# Zio_Qwiic_Air_Pressure_Sensor_BMP280.net
KiCad netlist of a schematic drawn in EAGLE
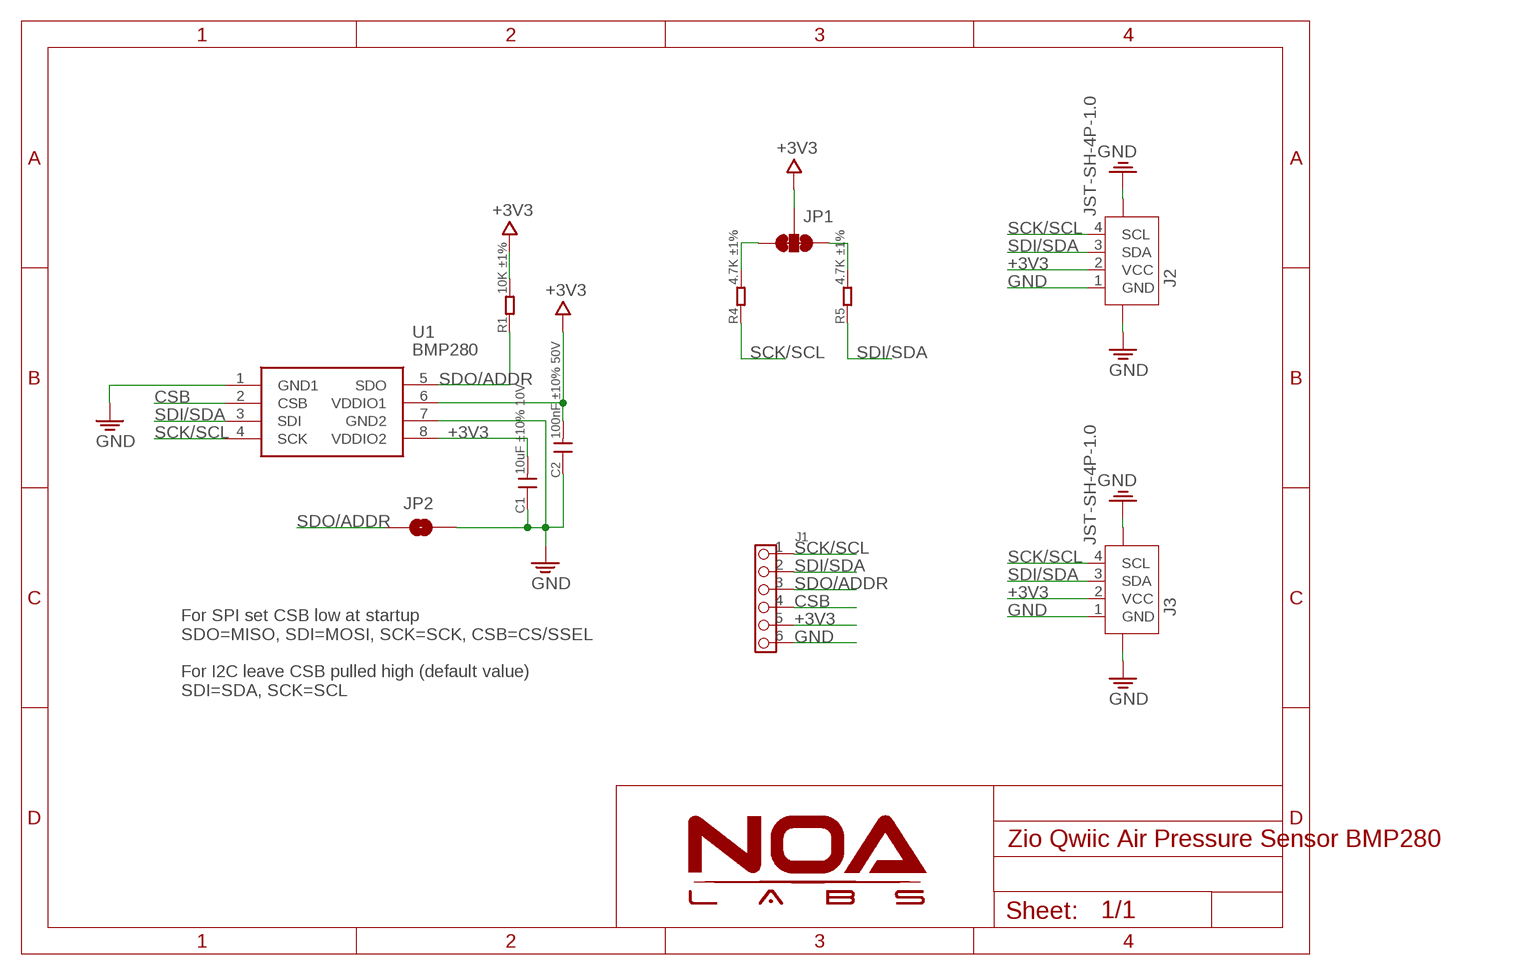
[diagram p0: schematic, sheet 1]

(export (version "E")
  (design (tool "Eeschema 10.0.6"))
  (components
    (comp (ref "C1")
      (value "10uF ±10% 10V")
      (footprint "eagle-import:C0603")
      (libsource (lib "eagle-import") (part "C-0603"))
    )
    (comp (ref "C2")
      (value "100nF ±10% 50V")
      (footprint "eagle-import:C0603")
      (libsource (lib "eagle-import") (part "C-0603"))
    )
    (comp (ref "J1")
      (value "HEADER-6P-60/35MIL")
      (footprint "eagle-import:6P-2.54-60_35MIL")
      (libsource (lib "eagle-import") (part "HEADER-6P-60/35MIL"))
    )
    (comp (ref "J2")
      (value "JST-SH-4P-1.0")
      (footprint "eagle-import:JST-SH-4P")
      (libsource (lib "eagle-import") (part "JST-SH-4P-1.0"))
    )
    (comp (ref "J3")
      (value "JST-SH-4P-1.0")
      (footprint "eagle-import:JST-SH-4P")
      (libsource (lib "eagle-import") (part "JST-SH-4P-1.0"))
    )
    (comp (ref "JP1")
      (value "SMT-JUMPER_3_2-NC_TRACE")
      (footprint "eagle-import:SMT-JUMPER_3_2-NC_TRACE")
      (libsource (lib "eagle-import") (part "SMT-JUMPER_3_2-NC_TRACE"))
    )
    (comp (ref "JP2")
      (value "JUMPER-SMT_2_NC_PASTE_NOCREM")
      (footprint "eagle-import:SMT-JUMPER_2_NC_PASTE_SILK_NOCREM")
      (libsource (lib "eagle-import") (part "JUMPER-SMT_2_NC_PASTE_NOCREM"))
    )
    (comp (ref "R1")
      (value "10K ±1%")
      (footprint "eagle-import:R0603")
      (libsource (lib "eagle-import") (part "R-0603"))
    )
    (comp (ref "R4")
      (value "4.7K ±1%")
      (footprint "eagle-import:R0603")
      (libsource (lib "eagle-import") (part "R-0603"))
    )
    (comp (ref "R5")
      (value "4.7K ±1%")
      (footprint "eagle-import:R0603")
      (libsource (lib "eagle-import") (part "R-0603"))
    )
    (comp (ref "U1")
      (value "BMP280")
      (footprint "eagle-import:8-PIN-METAL-LID-LGA")
      (fields (field (name "ARROW_PART_NUMBER") "bmp280"))
      (libsource (lib "eagle-import") (part "BMP280"))
    )
  )
  (nets
    (net (code "1") (name "+3V3") (class "Default")
      (node (ref "C1") (pin "2") (pinfunction "2_2") (pintype "passive"))
      (node (ref "C2") (pin "2") (pinfunction "2_2") (pintype "passive"))
      (node (ref "J1") (pin "5") (pinfunction "5_5") (pintype "bidirectional"))
      (node (ref "J2") (pin "2") (pinfunction "VCC_2") (pintype "bidirectional"))
      (node (ref "J3") (pin "2") (pinfunction "VCC_2") (pintype "bidirectional"))
      (node (ref "JP1") (pin "2") (pinfunction "2_2") (pintype "passive"))
      (node (ref "R1") (pin "2") (pinfunction "2_2") (pintype "passive"))
      (node (ref "U1") (pin "6") (pinfunction "VDDIO1_6") (pintype "power_in"))
      (node (ref "U1") (pin "8") (pinfunction "VDDIO2_8") (pintype "power_in"))
    )
    (net (code "2") (name "/CSB") (class "Default")
      (node (ref "J1") (pin "4") (pinfunction "4_4") (pintype "bidirectional"))
      (node (ref "U1") (pin "2") (pinfunction "CSB_2") (pintype "input"))
    )
    (net (code "3") (name "/SCK{slash}SCL") (class "Default")
      (node (ref "J1") (pin "1") (pinfunction "1_1") (pintype "bidirectional"))
      (node (ref "J2") (pin "4") (pinfunction "SCL_4") (pintype "bidirectional"))
      (node (ref "J3") (pin "4") (pinfunction "SCL_4") (pintype "bidirectional"))
      (node (ref "R4") (pin "1") (pinfunction "1_1") (pintype "passive"))
      (node (ref "U1") (pin "4") (pinfunction "SCK_4") (pintype "bidirectional"))
    )
    (net (code "4") (name "/SDI{slash}SDA") (class "Default")
      (node (ref "J1") (pin "2") (pinfunction "2_2") (pintype "bidirectional"))
      (node (ref "J2") (pin "3") (pinfunction "SDA_3") (pintype "bidirectional"))
      (node (ref "J3") (pin "3") (pinfunction "SDA_3") (pintype "bidirectional"))
      (node (ref "R5") (pin "1") (pinfunction "1_1") (pintype "passive"))
      (node (ref "U1") (pin "3") (pinfunction "SDI_3") (pintype "bidirectional"))
    )
    (net (code "5") (name "/SDO{slash}ADDR") (class "Default")
      (node (ref "J1") (pin "3") (pinfunction "3_3") (pintype "bidirectional"))
      (node (ref "JP2") (pin "1") (pinfunction "1_1") (pintype "passive"))
      (node (ref "R1") (pin "1") (pinfunction "1_1") (pintype "passive"))
      (node (ref "U1") (pin "5") (pinfunction "SDO_5") (pintype "bidirectional"))
    )
    (net (code "6") (name "GND") (class "Default")
      (node (ref "C1") (pin "1") (pinfunction "1_1") (pintype "passive"))
      (node (ref "C2") (pin "1") (pinfunction "1_1") (pintype "passive"))
      (node (ref "J1") (pin "6") (pinfunction "6_6") (pintype "bidirectional"))
      (node (ref "J2") (pin "1") (pinfunction "GND_1") (pintype "bidirectional"))
      (node (ref "J2") (pin "NC1") (pinfunction "5_NC1") (pintype "bidirectional"))
      (node (ref "J2") (pin "NC2") (pinfunction "6_NC2") (pintype "bidirectional"))
      (node (ref "J3") (pin "1") (pinfunction "GND_1") (pintype "bidirectional"))
      (node (ref "J3") (pin "NC1") (pinfunction "5_NC1") (pintype "bidirectional"))
      (node (ref "J3") (pin "NC2") (pinfunction "6_NC2") (pintype "bidirectional"))
      (node (ref "JP2") (pin "2") (pinfunction "2_2") (pintype "passive"))
      (node (ref "U1") (pin "1") (pinfunction "GND1_1") (pintype "power_in"))
      (node (ref "U1") (pin "7") (pinfunction "GND2_7") (pintype "power_in"))
    )
    (net (code "7") (name "Net-(JP1-Pad1)") (class "Default")
      (node (ref "JP1") (pin "1") (pinfunction "1_1") (pintype "passive"))
      (node (ref "R5") (pin "2") (pinfunction "2_2") (pintype "passive"))
    )
    (net (code "8") (name "Net-(JP1-Pad3)") (class "Default")
      (node (ref "JP1") (pin "3") (pinfunction "3_3") (pintype "passive"))
      (node (ref "R4") (pin "2") (pinfunction "2_2") (pintype "passive"))
    )
  )
)
